# IMX8_LPDDR4.net
KiCad netlist of a schematic drawn in Altium Designer
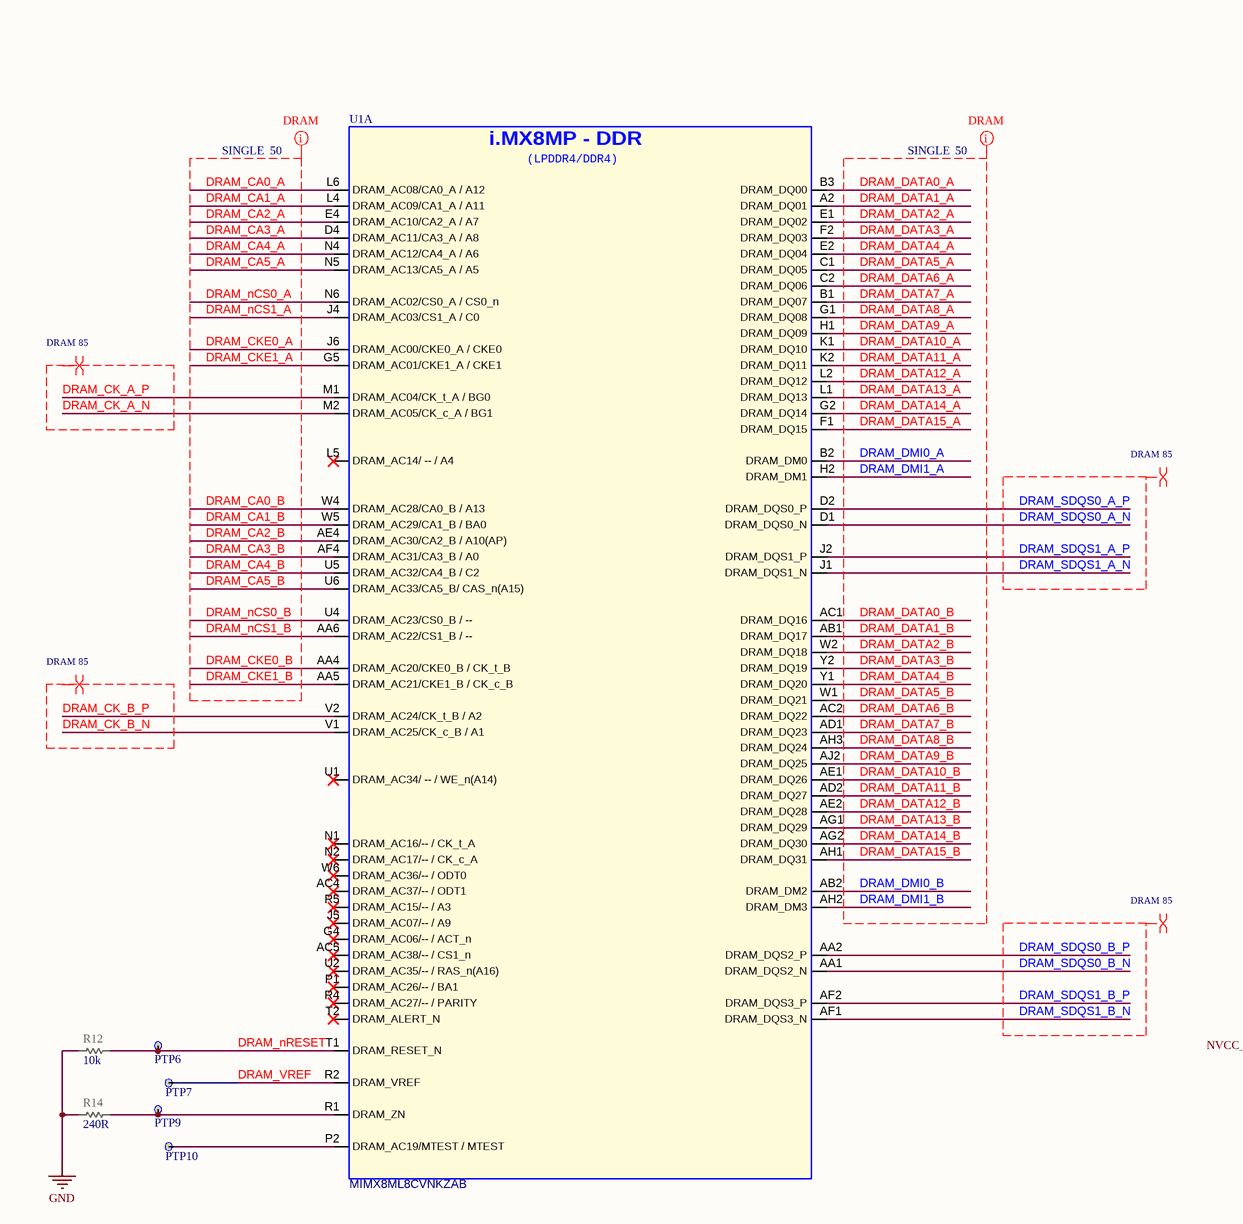
[diagram p0: IMX8_LPDDR4.SchDoc, top left]
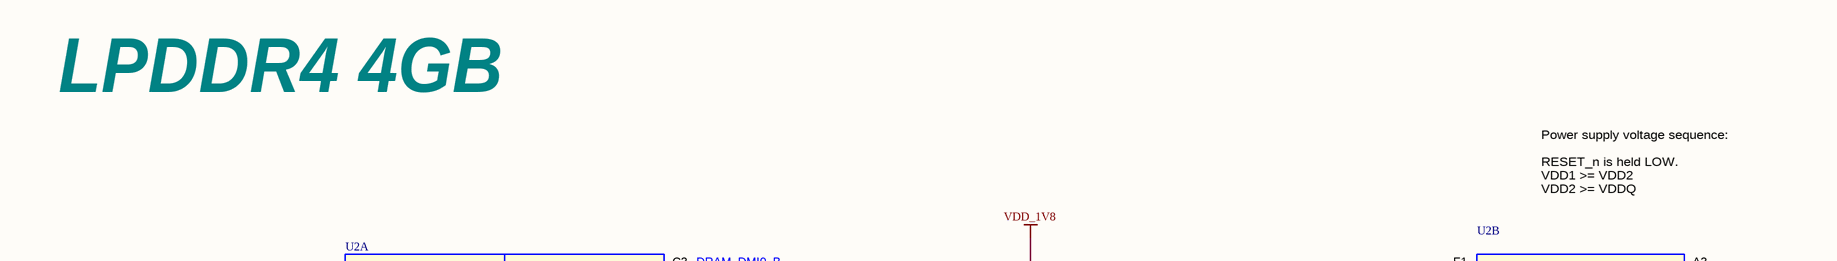
[diagram p1: IMX8_LPDDR4.SchDoc, top right]
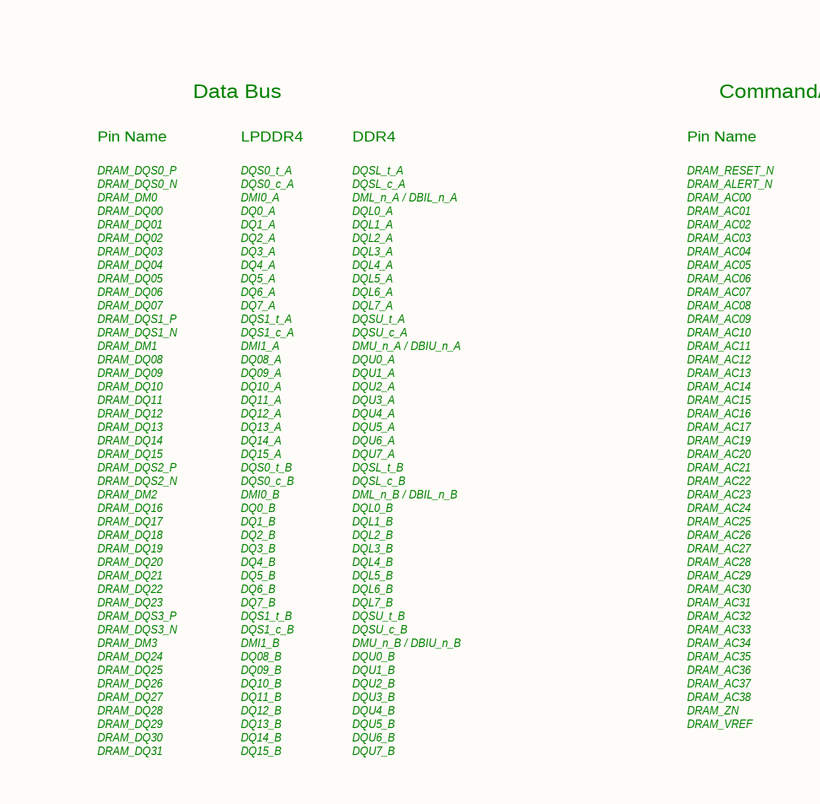
[diagram p2: IMX8_LPDDR4.SchDoc, bottom left]
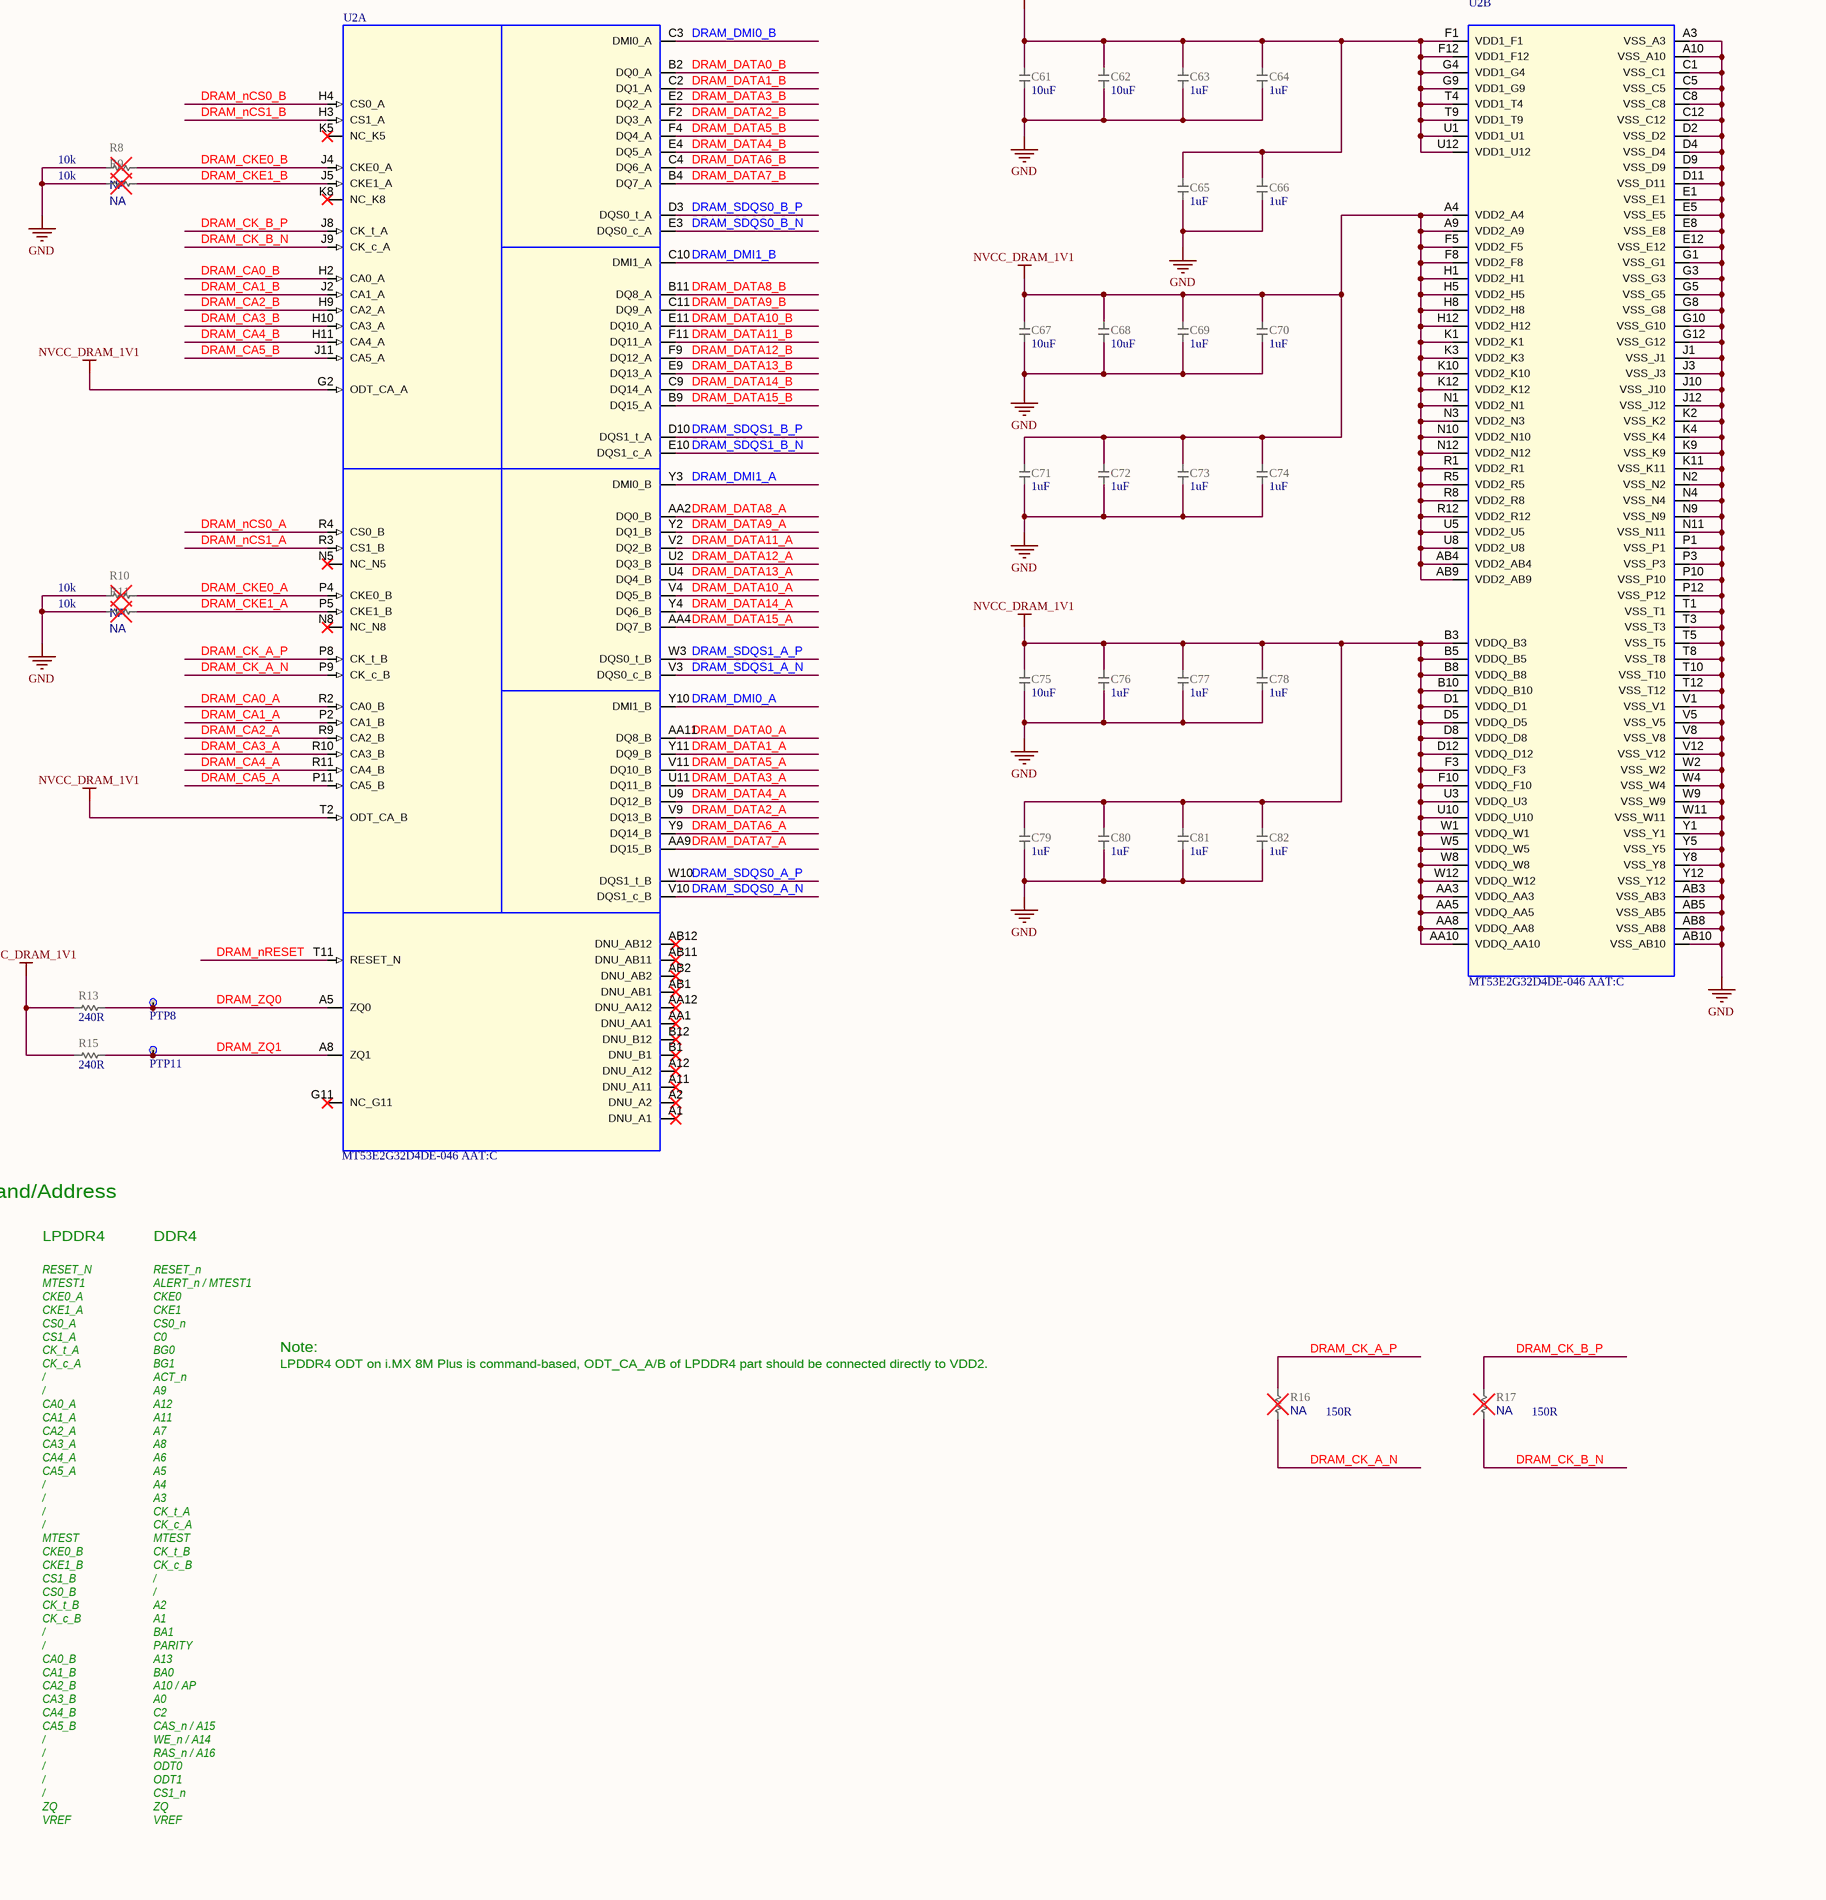
[diagram p3: IMX8_LPDDR4.SchDoc, bottom right]

(export (version "E")
  (design (tool "Eeschema 10.0.6"))
  (components
    (comp (ref "C61")
      (value "10uF")
      (footprint "CAP_0402_H09W07_UN1Q")
      (description "CAP")
      (fields (field (name "VOLTAGE") "6.3V") (field (name "TOLERANCE") "+/-20%"))
      (libsource (lib "robo_cam") (part "CMP-001-000883-14"))
    )
    (comp (ref "C62")
      (value "10uF")
      (footprint "CAP_0402_H09W07_UN1Q")
      (description "CAP")
      (fields (field (name "VOLTAGE") "6.3V") (field (name "TOLERANCE") "+/-20%"))
      (libsource (lib "robo_cam") (part "CMP-001-000883-14"))
    )
    (comp (ref "C63")
      (value "1uF")
      (footprint "CAP_0201_UN1Q")
      (description "CAP")
      (fields (field (name "PART NUMBER") "KGM03CS61A105MH") (field (name "MANUFACTURER") "KYOCERA AVX"))
      (libsource (lib "robo_cam") (part "CMP-001-000336-15"))
    )
    (comp (ref "C64")
      (value "1uF")
      (footprint "CAP_0201_UN1Q")
      (description "CAP")
      (fields (field (name "PART NUMBER") "KGM03CS61A105MH") (field (name "MANUFACTURER") "KYOCERA AVX"))
      (libsource (lib "robo_cam") (part "CMP-001-000336-15"))
    )
    (comp (ref "C65")
      (value "1uF")
      (footprint "CAP_0201_UN1Q")
      (description "CAP")
      (fields (field (name "PART NUMBER") "KGM03CS61A105MH") (field (name "MANUFACTURER") "KYOCERA AVX"))
      (libsource (lib "robo_cam") (part "CMP-001-000336-15"))
    )
    (comp (ref "C66")
      (value "1uF")
      (footprint "CAP_0201_UN1Q")
      (description "CAP")
      (fields (field (name "PART NUMBER") "KGM03CS61A105MH") (field (name "MANUFACTURER") "KYOCERA AVX"))
      (libsource (lib "robo_cam") (part "CMP-001-000336-15"))
    )
    (comp (ref "C67")
      (value "10uF")
      (footprint "CAP_0402_H09W07_UN1Q")
      (description "CAP")
      (fields (field (name "VOLTAGE") "6.3V") (field (name "TOLERANCE") "+/-20%"))
      (libsource (lib "robo_cam") (part "CMP-001-000883-14"))
    )
    (comp (ref "C68")
      (value "10uF")
      (footprint "CAP_0402_H09W07_UN1Q")
      (description "CAP")
      (fields (field (name "VOLTAGE") "6.3V") (field (name "TOLERANCE") "+/-20%"))
      (libsource (lib "robo_cam") (part "CMP-001-000883-14"))
    )
    (comp (ref "C69")
      (value "1uF")
      (footprint "CAP_0201_UN1Q")
      (description "CAP")
      (fields (field (name "PART NUMBER") "KGM03CS61A105MH") (field (name "MANUFACTURER") "KYOCERA AVX"))
      (libsource (lib "robo_cam") (part "CMP-001-000336-15"))
    )
    (comp (ref "C70")
      (value "1uF")
      (footprint "CAP_0201_UN1Q")
      (description "CAP")
      (fields (field (name "PART NUMBER") "KGM03CS61A105MH") (field (name "MANUFACTURER") "KYOCERA AVX"))
      (libsource (lib "robo_cam") (part "CMP-001-000336-15"))
    )
    (comp (ref "C71")
      (value "1uF")
      (footprint "CAP_0201_UN1Q")
      (description "CAP")
      (fields (field (name "PART NUMBER") "KGM03CS61A105MH") (field (name "MANUFACTURER") "KYOCERA AVX"))
      (libsource (lib "robo_cam") (part "CMP-001-000336-15"))
    )
    (comp (ref "C72")
      (value "1uF")
      (footprint "CAP_0201_UN1Q")
      (description "CAP")
      (fields (field (name "PART NUMBER") "KGM03CS61A105MH") (field (name "MANUFACTURER") "KYOCERA AVX"))
      (libsource (lib "robo_cam") (part "CMP-001-000336-15"))
    )
    (comp (ref "C73")
      (value "1uF")
      (footprint "CAP_0201_UN1Q")
      (description "CAP")
      (fields (field (name "PART NUMBER") "KGM03CS61A105MH") (field (name "MANUFACTURER") "KYOCERA AVX"))
      (libsource (lib "robo_cam") (part "CMP-001-000336-15"))
    )
    (comp (ref "C74")
      (value "1uF")
      (footprint "CAP_0201_UN1Q")
      (description "CAP")
      (fields (field (name "PART NUMBER") "KGM03CS61A105MH") (field (name "MANUFACTURER") "KYOCERA AVX"))
      (libsource (lib "robo_cam") (part "CMP-001-000336-15"))
    )
    (comp (ref "C75")
      (value "10uF")
      (footprint "CAP_0402_H09W07_UN1Q")
      (description "CAP")
      (fields (field (name "VOLTAGE") "6.3V") (field (name "TOLERANCE") "+/-20%"))
      (libsource (lib "robo_cam") (part "CMP-001-000883-14"))
    )
    (comp (ref "C76")
      (value "1uF")
      (footprint "CAP_0201_UN1Q")
      (description "CAP")
      (fields (field (name "PART NUMBER") "KGM03CS61A105MH") (field (name "MANUFACTURER") "KYOCERA AVX"))
      (libsource (lib "robo_cam") (part "CMP-001-000336-15"))
    )
    (comp (ref "C77")
      (value "1uF")
      (footprint "CAP_0201_UN1Q")
      (description "CAP")
      (fields (field (name "PART NUMBER") "KGM03CS61A105MH") (field (name "MANUFACTURER") "KYOCERA AVX"))
      (libsource (lib "robo_cam") (part "CMP-001-000336-15"))
    )
    (comp (ref "C78")
      (value "1uF")
      (footprint "CAP_0201_UN1Q")
      (description "CAP")
      (fields (field (name "PART NUMBER") "KGM03CS61A105MH") (field (name "MANUFACTURER") "KYOCERA AVX"))
      (libsource (lib "robo_cam") (part "CMP-001-000336-15"))
    )
    (comp (ref "C79")
      (value "1uF")
      (footprint "CAP_0201_UN1Q")
      (description "CAP")
      (fields (field (name "PART NUMBER") "KGM03CS61A105MH") (field (name "MANUFACTURER") "KYOCERA AVX"))
      (libsource (lib "robo_cam") (part "CMP-001-000336-15"))
    )
    (comp (ref "C80")
      (value "1uF")
      (footprint "CAP_0201_UN1Q")
      (description "CAP")
      (fields (field (name "PART NUMBER") "KGM03CS61A105MH") (field (name "MANUFACTURER") "KYOCERA AVX"))
      (libsource (lib "robo_cam") (part "CMP-001-000336-15"))
    )
    (comp (ref "C81")
      (value "1uF")
      (footprint "CAP_0201_UN1Q")
      (description "CAP")
      (fields (field (name "PART NUMBER") "KGM03CS61A105MH") (field (name "MANUFACTURER") "KYOCERA AVX"))
      (libsource (lib "robo_cam") (part "CMP-001-000336-15"))
    )
    (comp (ref "C82")
      (value "1uF")
      (footprint "CAP_0201_UN1Q")
      (description "CAP")
      (fields (field (name "PART NUMBER") "KGM03CS61A105MH") (field (name "MANUFACTURER") "KYOCERA AVX"))
      (libsource (lib "robo_cam") (part "CMP-001-000336-15"))
    )
    (comp (ref "PTP6")
      (value "PTP_0.4mm")
      (footprint "PTP_0.4mm")
      (description "Production Testpoint 0.4mm. Flying probe. Use 1mm pitch.")
      (fields (field (name "PART NUMBER") "PTP 0.4mm"))
      (libsource (lib "robo_cam") (part "CMP-001-001296-3"))
    )
    (comp (ref "PTP7")
      (value "PTP_0.4mm")
      (footprint "PTP_0.4mm")
      (description "Production Testpoint 0.4mm. Flying probe. Use 1mm pitch.")
      (fields (field (name "PART NUMBER") "PTP 0.4mm"))
      (libsource (lib "robo_cam") (part "CMP-001-001296-3"))
    )
    (comp (ref "PTP8")
      (value "PTP_0.4mm")
      (footprint "PTP_0.4mm")
      (description "Production Testpoint 0.4mm. Flying probe. Use 1mm pitch.")
      (fields (field (name "PART NUMBER") "PTP 0.4mm"))
      (libsource (lib "robo_cam") (part "CMP-001-001296-3"))
    )
    (comp (ref "PTP9")
      (value "PTP_0.4mm")
      (footprint "PTP_0.4mm")
      (description "Production Testpoint 0.4mm. Flying probe. Use 1mm pitch.")
      (fields (field (name "PART NUMBER") "PTP 0.4mm"))
      (libsource (lib "robo_cam") (part "CMP-001-001296-3"))
    )
    (comp (ref "PTP10")
      (value "PTP_0.4mm")
      (footprint "PTP_0.4mm")
      (description "Production Testpoint 0.4mm. Flying probe. Use 1mm pitch.")
      (fields (field (name "PART NUMBER") "PTP 0.4mm"))
      (libsource (lib "robo_cam") (part "CMP-001-001296-3"))
    )
    (comp (ref "PTP11")
      (value "PTP_0.4mm")
      (footprint "PTP_0.4mm")
      (description "Production Testpoint 0.4mm. Flying probe. Use 1mm pitch.")
      (fields (field (name "PART NUMBER") "PTP 0.4mm"))
      (libsource (lib "robo_cam") (part "CMP-001-001296-3"))
    )
    (comp (ref "R8")
      (value "NA")
      (footprint "RES_0201_UN1Q")
      (description "Not Assembled - RES")
      (fields (field (name "Comment") "RES_0201_NA"))
      (libsource (lib "robo_cam") (part "CMP-001-000434-10"))
    )
    (comp (ref "R9")
      (value "NA")
      (footprint "RES_0201_UN1Q")
      (description "Not Assembled - RES")
      (fields (field (name "Comment") "RES_0201_NA"))
      (libsource (lib "robo_cam") (part "CMP-001-000434-10"))
    )
    (comp (ref "R10")
      (value "NA")
      (footprint "RES_0201_UN1Q")
      (description "Not Assembled - RES")
      (fields (field (name "Comment") "RES_0201_NA"))
      (libsource (lib "robo_cam") (part "CMP-001-000434-10"))
    )
    (comp (ref "R11")
      (value "NA")
      (footprint "RES_0201_UN1Q")
      (description "Not Assembled - RES")
      (fields (field (name "Comment") "RES_0201_NA"))
      (libsource (lib "robo_cam") (part "CMP-001-000434-10"))
    )
    (comp (ref "R12")
      (value "10k")
      (footprint "RES_0201_UN1Q")
      (description "RES")
      (fields (field (name "PART NUMBER") "RC0201FR-0710KL") (field (name "MANUFACTURER") "YAGEO"))
      (libsource (lib "robo_cam") (part "CMP-001-000446-13"))
    )
    (comp (ref "R13")
      (value "240R")
      (footprint "RES_0201_UN1Q")
      (description "RES")
      (fields (field (name "TOLERANCE") "1%") (field (name "PART NUMBER") "ERJ-1GEJ241C"))
      (libsource (lib "robo_cam") (part "CMP-001-000554-13"))
    )
    (comp (ref "R14")
      (value "240R")
      (footprint "RES_0201_UN1Q")
      (description "RES")
      (fields (field (name "TOLERANCE") "1%") (field (name "PART NUMBER") "ERJ-1GEJ241C"))
      (libsource (lib "robo_cam") (part "CMP-001-000554-13"))
    )
    (comp (ref "R15")
      (value "240R")
      (footprint "RES_0201_UN1Q")
      (description "RES")
      (fields (field (name "TOLERANCE") "1%") (field (name "PART NUMBER") "ERJ-1GEJ241C"))
      (libsource (lib "robo_cam") (part "CMP-001-000554-13"))
    )
    (comp (ref "R16")
      (value "NA")
      (footprint "RES_0201_UN1Q")
      (description "Not Assembled - RES")
      (fields (field (name "Comment") "RES_0201_NA"))
      (libsource (lib "robo_cam") (part "CMP-001-000434-10"))
    )
    (comp (ref "R17")
      (value "NA")
      (footprint "RES_0201_UN1Q")
      (description "Not Assembled - RES")
      (fields (field (name "Comment") "RES_0201_NA"))
      (libsource (lib "robo_cam") (part "CMP-001-000434-10"))
    )
    (comp (ref "U1")
      (value "MIMX8ML8CVNKZAB")
      (footprint "BGA548C50P29X29_1500X1500X148")
      (description "CPU QUAD CORTEX A53+M4 1.6GHZ BGA548 Industrial")
      (fields
        (field (name "MANUFACTURER") "NXP Semiconductors")
        (field (name "PART NUMBER") "MIMX8ML8CVNKZAB")
        (field (name "SOURCE") "UUDET_KOMPONENTIT.SchLib")
      )
      (libsource (lib "robo_cam") (part "CMP-001-000983-8"))
    )
    (comp (ref "U2")
      (value "MT53E2G32D4DE-046 AAT:C")
      (footprint "BGA200C65P12X22_1000X1450X114")
      (description "MEM LPDDR4 SDRAM 2133MHz 2Gx32Gb 1.1V")
      (fields (field (name "MANUFACTURER") "Micron") (field (name "PART NUMBER") "MT53E2G32D4DE-046 AAT:C"))
      (libsource (lib "robo_cam") (part "CMP-001-001446-1"))
    )
  )
  (nets
    (net (code "1") (name "/DRAM_CA0_A") (class "Default")
      (node (ref "U1") (pin "L6") (pinfunction "DRAM_AC08/CA0_A_/_A12_L6") (pintype "passive"))
      (node (ref "U2") (pin "R2") (pinfunction "CA0_B_R2") (pintype "input"))
    )
    (net (code "2") (name "/DRAM_CA0_B") (class "Default")
      (node (ref "U1") (pin "W4") (pinfunction "DRAM_AC28/CA0_B_/_A13_W4") (pintype "passive"))
      (node (ref "U2") (pin "H2") (pinfunction "CA0_A_H2") (pintype "input"))
    )
    (net (code "3") (name "/DRAM_CA1_A") (class "Default")
      (node (ref "U1") (pin "L4") (pinfunction "DRAM_AC09/CA1_A_/_A11_L4") (pintype "passive"))
      (node (ref "U2") (pin "P2") (pinfunction "CA1_B_P2") (pintype "input"))
    )
    (net (code "4") (name "/DRAM_CA1_B") (class "Default")
      (node (ref "U1") (pin "W5") (pinfunction "DRAM_AC29/CA1_B_/_BA0_W5") (pintype "passive"))
      (node (ref "U2") (pin "J2") (pinfunction "CA1_A_J2") (pintype "input"))
    )
    (net (code "5") (name "/DRAM_CA2_A") (class "Default")
      (node (ref "U1") (pin "E4") (pinfunction "DRAM_AC10/CA2_A_/_A7_E4") (pintype "passive"))
      (node (ref "U2") (pin "R9") (pinfunction "CA2_B_R9") (pintype "input"))
    )
    (net (code "6") (name "/DRAM_CA2_B") (class "Default")
      (node (ref "U1") (pin "AE4") (pinfunction "DRAM_AC30/CA2_B_/_A10(AP)_AE4") (pintype "passive"))
      (node (ref "U2") (pin "H9") (pinfunction "CA2_A_H9") (pintype "input"))
    )
    (net (code "7") (name "/DRAM_CA3_A") (class "Default")
      (node (ref "U1") (pin "D4") (pinfunction "DRAM_AC11/CA3_A_/_A8_D4") (pintype "passive"))
      (node (ref "U2") (pin "R10") (pinfunction "CA3_B_R10") (pintype "input"))
    )
    (net (code "8") (name "/DRAM_CA3_B") (class "Default")
      (node (ref "U1") (pin "AF4") (pinfunction "DRAM_AC31/CA3_B_/_A0_AF4") (pintype "passive"))
      (node (ref "U2") (pin "H10") (pinfunction "CA3_A_H10") (pintype "input"))
    )
    (net (code "9") (name "/DRAM_CA4_A") (class "Default")
      (node (ref "U1") (pin "N4") (pinfunction "DRAM_AC12/CA4_A_/_A6_N4") (pintype "passive"))
      (node (ref "U2") (pin "R11") (pinfunction "CA4_B_R11") (pintype "input"))
    )
    (net (code "10") (name "/DRAM_CA4_B") (class "Default")
      (node (ref "U1") (pin "U5") (pinfunction "DRAM_AC32/CA4_B_/_C2_U5") (pintype "passive"))
      (node (ref "U2") (pin "H11") (pinfunction "CA4_A_H11") (pintype "input"))
    )
    (net (code "11") (name "/DRAM_CA5_A") (class "Default")
      (node (ref "U1") (pin "N5") (pinfunction "DRAM_AC13/CA5_A_/_A5_N5") (pintype "passive"))
      (node (ref "U2") (pin "P11") (pinfunction "CA5_B_P11") (pintype "input"))
    )
    (net (code "12") (name "/DRAM_CA5_B") (class "Default")
      (node (ref "U1") (pin "U6") (pinfunction "DRAM_AC33/CA5_B/_CAS_n(A15)_U6") (pintype "passive"))
      (node (ref "U2") (pin "J11") (pinfunction "CA5_A_J11") (pintype "input"))
    )
    (net (code "13") (name "/DRAM_CKE0_A") (class "Default")
      (node (ref "R10") (pin "2") (pinfunction "2_2") (pintype "passive"))
      (node (ref "U1") (pin "J6") (pinfunction "DRAM_AC00/CKE0_A_/_CKE0_J6") (pintype "passive"))
      (node (ref "U2") (pin "P4") (pinfunction "CKE0_B_P4") (pintype "input"))
    )
    (net (code "14") (name "/DRAM_CKE0_B") (class "Default")
      (node (ref "R8") (pin "2") (pinfunction "2_2") (pintype "passive"))
      (node (ref "U1") (pin "AA4") (pinfunction "DRAM_AC20/CKE0_B_/_CK_t_B_AA4") (pintype "passive"))
      (node (ref "U2") (pin "J4") (pinfunction "CKE0_A_J4") (pintype "input"))
    )
    (net (code "15") (name "/DRAM_CKE1_A") (class "Default")
      (node (ref "R11") (pin "2") (pinfunction "2_2") (pintype "passive"))
      (node (ref "U1") (pin "G5") (pinfunction "DRAM_AC01/CKE1_A_/_CKE1_G5") (pintype "passive"))
      (node (ref "U2") (pin "P5") (pinfunction "CKE1_B_P5") (pintype "input"))
    )
    (net (code "16") (name "/DRAM_CKE1_B") (class "Default")
      (node (ref "R9") (pin "2") (pinfunction "2_2") (pintype "passive"))
      (node (ref "U1") (pin "AA5") (pinfunction "DRAM_AC21/CKE1_B_/_CK_c_B_AA5") (pintype "passive"))
      (node (ref "U2") (pin "J5") (pinfunction "CKE1_A_J5") (pintype "input"))
    )
    (net (code "17") (name "/DRAM_CK_A_N") (class "Default")
      (node (ref "R16") (pin "1") (pinfunction "1_1") (pintype "passive"))
      (node (ref "U1") (pin "M2") (pinfunction "DRAM_AC05/CK_c_A_/_BG1_M2") (pintype "passive"))
      (node (ref "U2") (pin "P9") (pinfunction "CK_c_B_P9") (pintype "input"))
    )
    (net (code "18") (name "/DRAM_CK_A_P") (class "Default")
      (node (ref "R16") (pin "2") (pinfunction "2_2") (pintype "passive"))
      (node (ref "U1") (pin "M1") (pinfunction "DRAM_AC04/CK_t_A_/_BG0_M1") (pintype "passive"))
      (node (ref "U2") (pin "P8") (pinfunction "CK_t_B_P8") (pintype "input"))
    )
    (net (code "19") (name "/DRAM_CK_B_N") (class "Default")
      (node (ref "R17") (pin "1") (pinfunction "1_1") (pintype "passive"))
      (node (ref "U1") (pin "V1") (pinfunction "DRAM_AC25/CK_c_B_/_A1_V1") (pintype "passive"))
      (node (ref "U2") (pin "J9") (pinfunction "CK_c_A_J9") (pintype "input"))
    )
    (net (code "20") (name "/DRAM_CK_B_P") (class "Default")
      (node (ref "R17") (pin "2") (pinfunction "2_2") (pintype "passive"))
      (node (ref "U1") (pin "V2") (pinfunction "DRAM_AC24/CK_t_B_/_A2_V2") (pintype "passive"))
      (node (ref "U2") (pin "J8") (pinfunction "CK_t_A_J8") (pintype "input"))
    )
    (net (code "21") (name "/DRAM_DATA0_A") (class "Default")
      (node (ref "U1") (pin "B3") (pinfunction "DRAM_DQ00_B3") (pintype "passive"))
      (node (ref "U2") (pin "AA11") (pinfunction "DQ8_B_AA11") (pintype "bidirectional"))
    )
    (net (code "22") (name "/DRAM_DATA0_B") (class "Default")
      (node (ref "U1") (pin "AC1") (pinfunction "DRAM_DQ16_AC1") (pintype "passive"))
      (node (ref "U2") (pin "B2") (pinfunction "DQ0_A_B2") (pintype "bidirectional"))
    )
    (net (code "23") (name "/DRAM_DATA1_A") (class "Default")
      (node (ref "U1") (pin "A2") (pinfunction "DRAM_DQ01_A2") (pintype "passive"))
      (node (ref "U2") (pin "Y11") (pinfunction "DQ9_B_Y11") (pintype "bidirectional"))
    )
    (net (code "24") (name "/DRAM_DATA1_B") (class "Default")
      (node (ref "U1") (pin "AB1") (pinfunction "DRAM_DQ17_AB1") (pintype "passive"))
      (node (ref "U2") (pin "C2") (pinfunction "DQ1_A_C2") (pintype "bidirectional"))
    )
    (net (code "25") (name "/DRAM_DATA2_A") (class "Default")
      (node (ref "U1") (pin "E1") (pinfunction "DRAM_DQ02_E1") (pintype "passive"))
      (node (ref "U2") (pin "V9") (pinfunction "DQ13_B_V9") (pintype "bidirectional"))
    )
    (net (code "26") (name "/DRAM_DATA2_B") (class "Default")
      (node (ref "U1") (pin "W2") (pinfunction "DRAM_DQ18_W2") (pintype "passive"))
      (node (ref "U2") (pin "F2") (pinfunction "DQ3_A_F2") (pintype "bidirectional"))
    )
    (net (code "27") (name "/DRAM_DATA3_A") (class "Default")
      (node (ref "U1") (pin "F2") (pinfunction "DRAM_DQ03_F2") (pintype "passive"))
      (node (ref "U2") (pin "U11") (pinfunction "DQ11_B_U11") (pintype "bidirectional"))
    )
    (net (code "28") (name "/DRAM_DATA3_B") (class "Default")
      (node (ref "U1") (pin "Y2") (pinfunction "DRAM_DQ19_Y2") (pintype "passive"))
      (node (ref "U2") (pin "E2") (pinfunction "DQ2_A_E2") (pintype "bidirectional"))
    )
    (net (code "29") (name "/DRAM_DATA4_A") (class "Default")
      (node (ref "U1") (pin "E2") (pinfunction "DRAM_DQ04_E2") (pintype "passive"))
      (node (ref "U2") (pin "U9") (pinfunction "DQ12_B_U9") (pintype "bidirectional"))
    )
    (net (code "30") (name "/DRAM_DATA4_B") (class "Default")
      (node (ref "U1") (pin "Y1") (pinfunction "DRAM_DQ20_Y1") (pintype "passive"))
      (node (ref "U2") (pin "E4") (pinfunction "DQ5_A_E4") (pintype "bidirectional"))
    )
    (net (code "31") (name "/DRAM_DATA5_A") (class "Default")
      (node (ref "U1") (pin "C1") (pinfunction "DRAM_DQ05_C1") (pintype "passive"))
      (node (ref "U2") (pin "V11") (pinfunction "DQ10_B_V11") (pintype "bidirectional"))
    )
    (net (code "32") (name "/DRAM_DATA5_B") (class "Default")
      (node (ref "U1") (pin "W1") (pinfunction "DRAM_DQ21_W1") (pintype "passive"))
      (node (ref "U2") (pin "F4") (pinfunction "DQ4_A_F4") (pintype "bidirectional"))
    )
    (net (code "33") (name "/DRAM_DATA6_A") (class "Default")
      (node (ref "U1") (pin "C2") (pinfunction "DRAM_DQ06_C2") (pintype "passive"))
      (node (ref "U2") (pin "Y9") (pinfunction "DQ14_B_Y9") (pintype "bidirectional"))
    )
    (net (code "34") (name "/DRAM_DATA6_B") (class "Default")
      (node (ref "U1") (pin "AC2") (pinfunction "DRAM_DQ22_AC2") (pintype "passive"))
      (node (ref "U2") (pin "C4") (pinfunction "DQ6_A_C4") (pintype "bidirectional"))
    )
    (net (code "35") (name "/DRAM_DATA7_A") (class "Default")
      (node (ref "U1") (pin "B1") (pinfunction "DRAM_DQ07_B1") (pintype "passive"))
      (node (ref "U2") (pin "AA9") (pinfunction "DQ15_B_AA9") (pintype "bidirectional"))
    )
    (net (code "36") (name "/DRAM_DATA7_B") (class "Default")
      (node (ref "U1") (pin "AD1") (pinfunction "DRAM_DQ23_AD1") (pintype "passive"))
      (node (ref "U2") (pin "B4") (pinfunction "DQ7_A_B4") (pintype "bidirectional"))
    )
    (net (code "37") (name "/DRAM_DATA8_A") (class "Default")
      (node (ref "U1") (pin "G1") (pinfunction "DRAM_DQ08_G1") (pintype "passive"))
      (node (ref "U2") (pin "AA2") (pinfunction "DQ0_B_AA2") (pintype "bidirectional"))
    )
    (net (code "38") (name "/DRAM_DATA8_B") (class "Default")
      (node (ref "U1") (pin "AH3") (pinfunction "DRAM_DQ24_AH3") (pintype "passive"))
      (node (ref "U2") (pin "B11") (pinfunction "DQ8_A_B11") (pintype "bidirectional"))
    )
    (net (code "39") (name "/DRAM_DATA9_A") (class "Default")
      (node (ref "U1") (pin "H1") (pinfunction "DRAM_DQ09_H1") (pintype "passive"))
      (node (ref "U2") (pin "Y2") (pinfunction "DQ1_B_Y2") (pintype "bidirectional"))
    )
    (net (code "40") (name "/DRAM_DATA9_B") (class "Default")
      (node (ref "U1") (pin "AJ2") (pinfunction "DRAM_DQ25_AJ2") (pintype "passive"))
      (node (ref "U2") (pin "C11") (pinfunction "DQ9_A_C11") (pintype "bidirectional"))
    )
    (net (code "41") (name "/DRAM_DATA10_A") (class "Default")
      (node (ref "U1") (pin "K1") (pinfunction "DRAM_DQ10_K1") (pintype "passive"))
      (node (ref "U2") (pin "V4") (pinfunction "DQ5_B_V4") (pintype "bidirectional"))
    )
    (net (code "42") (name "/DRAM_DATA10_B") (class "Default")
      (node (ref "U1") (pin "AE1") (pinfunction "DRAM_DQ26_AE1") (pintype "passive"))
      (node (ref "U2") (pin "E11") (pinfunction "DQ10_A_E11") (pintype "bidirectional"))
    )
    (net (code "43") (name "/DRAM_DATA11_A") (class "Default")
      (node (ref "U1") (pin "K2") (pinfunction "DRAM_DQ11_K2") (pintype "passive"))
      (node (ref "U2") (pin "V2") (pinfunction "DQ2_B_V2") (pintype "bidirectional"))
    )
    (net (code "44") (name "/DRAM_DATA11_B") (class "Default")
      (node (ref "U1") (pin "AD2") (pinfunction "DRAM_DQ27_AD2") (pintype "passive"))
      (node (ref "U2") (pin "F11") (pinfunction "DQ11_A_F11") (pintype "bidirectional"))
    )
    (net (code "45") (name "/DRAM_DATA12_A") (class "Default")
      (node (ref "U1") (pin "L2") (pinfunction "DRAM_DQ12_L2") (pintype "passive"))
      (node (ref "U2") (pin "U2") (pinfunction "DQ3_B_U2") (pintype "bidirectional"))
    )
    (net (code "46") (name "/DRAM_DATA12_B") (class "Default")
      (node (ref "U1") (pin "AE2") (pinfunction "DRAM_DQ28_AE2") (pintype "passive"))
      (node (ref "U2") (pin "F9") (pinfunction "DQ12_A_F9") (pintype "bidirectional"))
    )
    (net (code "47") (name "/DRAM_DATA13_A") (class "Default")
      (node (ref "U1") (pin "L1") (pinfunction "DRAM_DQ13_L1") (pintype "passive"))
      (node (ref "U2") (pin "U4") (pinfunction "DQ4_B_U4") (pintype "bidirectional"))
    )
    (net (code "48") (name "/DRAM_DATA13_B") (class "Default")
      (node (ref "U1") (pin "AG1") (pinfunction "DRAM_DQ29_AG1") (pintype "passive"))
      (node (ref "U2") (pin "E9") (pinfunction "DQ13_A_E9") (pintype "bidirectional"))
    )
    (net (code "49") (name "/DRAM_DATA14_A") (class "Default")
      (node (ref "U1") (pin "G2") (pinfunction "DRAM_DQ14_G2") (pintype "passive"))
      (node (ref "U2") (pin "Y4") (pinfunction "DQ6_B_Y4") (pintype "bidirectional"))
    )
    (net (code "50") (name "/DRAM_DATA14_B") (class "Default")
      (node (ref "U1") (pin "AG2") (pinfunction "DRAM_DQ30_AG2") (pintype "passive"))
      (node (ref "U2") (pin "C9") (pinfunction "DQ14_A_C9") (pintype "bidirectional"))
    )
    (net (code "51") (name "/DRAM_DATA15_A") (class "Default")
      (node (ref "U1") (pin "F1") (pinfunction "DRAM_DQ15_F1") (pintype "passive"))
      (node (ref "U2") (pin "AA4") (pinfunction "DQ7_B_AA4") (pintype "bidirectional"))
    )
    (net (code "52") (name "/DRAM_DATA15_B") (class "Default")
      (node (ref "U1") (pin "AH1") (pinfunction "DRAM_DQ31_AH1") (pintype "passive"))
      (node (ref "U2") (pin "B9") (pinfunction "DQ15_A_B9") (pintype "bidirectional"))
    )
    (net (code "53") (name "/DRAM_DMI0_A") (class "Default")
      (node (ref "U1") (pin "B2") (pinfunction "DRAM_DM0_B2") (pintype "passive"))
      (node (ref "U2") (pin "Y10") (pinfunction "DMI1_B_Y10") (pintype "bidirectional"))
    )
    (net (code "54") (name "/DRAM_DMI0_B") (class "Default")
      (node (ref "U1") (pin "AB2") (pinfunction "DRAM_DM2_AB2") (pintype "passive"))
      (node (ref "U2") (pin "C3") (pinfunction "DMI0_A_C3") (pintype "bidirectional"))
    )
    (net (code "55") (name "/DRAM_DMI1_A") (class "Default")
      (node (ref "U1") (pin "H2") (pinfunction "DRAM_DM1_H2") (pintype "passive"))
      (node (ref "U2") (pin "Y3") (pinfunction "DMI0_B_Y3") (pintype "bidirectional"))
    )
    (net (code "56") (name "/DRAM_DMI1_B") (class "Default")
      (node (ref "U1") (pin "AH2") (pinfunction "DRAM_DM3_AH2") (pintype "passive"))
      (node (ref "U2") (pin "C10") (pinfunction "DMI1_A_C10") (pintype "bidirectional"))
    )
    (net (code "57") (name "/DRAM_SDQS0_A_N") (class "Default")
      (node (ref "U1") (pin "D1") (pinfunction "DRAM_DQS0_N_D1") (pintype "passive"))
      (node (ref "U2") (pin "V10") (pinfunction "DQS1_c_B_V10") (pintype "bidirectional"))
    )
    (net (code "58") (name "/DRAM_SDQS0_A_P") (class "Default")
      (node (ref "U1") (pin "D2") (pinfunction "DRAM_DQS0_P_D2") (pintype "passive"))
      (node (ref "U2") (pin "W10") (pinfunction "DQS1_t_B_W10") (pintype "bidirectional"))
    )
    (net (code "59") (name "/DRAM_SDQS0_B_N") (class "Default")
      (node (ref "U1") (pin "AA1") (pinfunction "DRAM_DQS2_N_AA1") (pintype "passive"))
      (node (ref "U2") (pin "E3") (pinfunction "DQS0_c_A_E3") (pintype "bidirectional"))
    )
    (net (code "60") (name "/DRAM_SDQS0_B_P") (class "Default")
      (node (ref "U1") (pin "AA2") (pinfunction "DRAM_DQS2_P_AA2") (pintype "passive"))
      (node (ref "U2") (pin "D3") (pinfunction "DQS0_t_A_D3") (pintype "bidirectional"))
    )
    (net (code "61") (name "/DRAM_SDQS1_A_N") (class "Default")
      (node (ref "U1") (pin "J1") (pinfunction "DRAM_DQS1_N_J1") (pintype "passive"))
      (node (ref "U2") (pin "V3") (pinfunction "DQS0_c_B_V3") (pintype "bidirectional"))
    )
    (net (code "62") (name "/DRAM_SDQS1_A_P") (class "Default")
      (node (ref "U1") (pin "J2") (pinfunction "DRAM_DQS1_P_J2") (pintype "passive"))
      (node (ref "U2") (pin "W3") (pinfunction "DQS0_t_B_W3") (pintype "bidirectional"))
    )
    (net (code "63") (name "/DRAM_SDQS1_B_N") (class "Default")
      (node (ref "U1") (pin "AF1") (pinfunction "DRAM_DQS3_N_AF1") (pintype "passive"))
      (node (ref "U2") (pin "E10") (pinfunction "DQS1_c_A_E10") (pintype "bidirectional"))
    )
    (net (code "64") (name "/DRAM_SDQS1_B_P") (class "Default")
      (node (ref "U1") (pin "AF2") (pinfunction "DRAM_DQS3_P_AF2") (pintype "passive"))
      (node (ref "U2") (pin "D10") (pinfunction "DQS1_t_A_D10") (pintype "bidirectional"))
    )
    (net (code "65") (name "/DRAM_VREF") (class "Default")
      (node (ref "PTP7") (pin "1") (pinfunction "TP_1") (pintype "passive"))
      (node (ref "U1") (pin "R2") (pinfunction "DRAM_VREF_R2") (pintype "passive"))
    )
    (net (code "66") (name "/DRAM_ZQ0") (class "Default")
      (node (ref "PTP8") (pin "1") (pinfunction "TP_1") (pintype "passive"))
      (node (ref "R13") (pin "2") (pinfunction "2_2") (pintype "passive"))
      (node (ref "U2") (pin "A5") (pinfunction "ZQ0_A5") (pintype "passive"))
    )
    (net (code "67") (name "/DRAM_ZQ1") (class "Default")
      (node (ref "PTP11") (pin "1") (pinfunction "TP_1") (pintype "passive"))
      (node (ref "R15") (pin "2") (pinfunction "2_2") (pintype "passive"))
      (node (ref "U2") (pin "A8") (pinfunction "ZQ1_A8") (pintype "passive"))
    )
    (net (code "68") (name "/DRAM_nCS0_A") (class "Default")
      (node (ref "U1") (pin "N6") (pinfunction "DRAM_AC02/CS0_A_/_CS0_n_N6") (pintype "passive"))
      (node (ref "U2") (pin "R4") (pinfunction "CS0_B_R4") (pintype "input"))
    )
    (net (code "69") (name "/DRAM_nCS0_B") (class "Default")
      (node (ref "U1") (pin "U4") (pinfunction "DRAM_AC23/CS0_B_/_--_U4") (pintype "passive"))
      (node (ref "U2") (pin "H4") (pinfunction "CS0_A_H4") (pintype "input"))
    )
    (net (code "70") (name "/DRAM_nCS1_A") (class "Default")
      (node (ref "U1") (pin "J4") (pinfunction "DRAM_AC03/CS1_A_/_C0_J4") (pintype "passive"))
      (node (ref "U2") (pin "R3") (pinfunction "CS1_B_R3") (pintype "input"))
    )
    (net (code "71") (name "/DRAM_nCS1_B") (class "Default")
      (node (ref "U1") (pin "AA6") (pinfunction "DRAM_AC22/CS1_B_/_--_AA6") (pintype "passive"))
      (node (ref "U2") (pin "H3") (pinfunction "CS1_A_H3") (pintype "input"))
    )
    (net (code "72") (name "/DRAM_nRESET") (class "Default")
      (node (ref "PTP6") (pin "1") (pinfunction "TP_1") (pintype "passive"))
      (node (ref "R12") (pin "2") (pinfunction "2_2") (pintype "passive"))
      (node (ref "U1") (pin "T1") (pinfunction "DRAM_RESET_N_T1") (pintype "passive"))
      (node (ref "U2") (pin "T11") (pinfunction "RESET_N_T11") (pintype "input"))
    )
    (net (code "73") (name "GND") (class "Default")
      (node (ref "C61") (pin "2") (pinfunction "2_2") (pintype "passive"))
      (node (ref "C62") (pin "2") (pinfunction "2_2") (pintype "passive"))
      (node (ref "C63") (pin "2") (pinfunction "2_2") (pintype "passive"))
      (node (ref "C64") (pin "2") (pinfunction "2_2") (pintype "passive"))
      (node (ref "C65") (pin "2") (pinfunction "2_2") (pintype "passive"))
      (node (ref "C66") (pin "2") (pinfunction "2_2") (pintype "passive"))
      (node (ref "C67") (pin "2") (pinfunction "2_2") (pintype "passive"))
      (node (ref "C68") (pin "2") (pinfunction "2_2") (pintype "passive"))
      (node (ref "C69") (pin "2") (pinfunction "2_2") (pintype "passive"))
      (node (ref "C70") (pin "2") (pinfunction "2_2") (pintype "passive"))
      (node (ref "C71") (pin "2") (pinfunction "2_2") (pintype "passive"))
      (node (ref "C72") (pin "2") (pinfunction "2_2") (pintype "passive"))
      (node (ref "C73") (pin "2") (pinfunction "2_2") (pintype "passive"))
      (node (ref "C74") (pin "2") (pinfunction "2_2") (pintype "passive"))
      (node (ref "C75") (pin "2") (pinfunction "2_2") (pintype "passive"))
      (node (ref "C76") (pin "2") (pinfunction "2_2") (pintype "passive"))
      (node (ref "C77") (pin "2") (pinfunction "2_2") (pintype "passive"))
      (node (ref "C78") (pin "2") (pinfunction "2_2") (pintype "passive"))
      (node (ref "C79") (pin "2") (pinfunction "2_2") (pintype "passive"))
      (node (ref "C80") (pin "2") (pinfunction "2_2") (pintype "passive"))
      (node (ref "C81") (pin "2") (pinfunction "2_2") (pintype "passive"))
      (node (ref "C82") (pin "2") (pinfunction "2_2") (pintype "passive"))
      (node (ref "R10") (pin "1") (pinfunction "1_1") (pintype "passive"))
      (node (ref "R11") (pin "1") (pinfunction "1_1") (pintype "passive"))
      (node (ref "R12") (pin "1") (pinfunction "1_1") (pintype "passive"))
      (node (ref "R14") (pin "1") (pinfunction "1_1") (pintype "passive"))
      (node (ref "R8") (pin "1") (pinfunction "1_1") (pintype "passive"))
      (node (ref "R9") (pin "1") (pinfunction "1_1") (pintype "passive"))
      (node (ref "U2") (pin "A10") (pinfunction "VSS_A10_A10") (pintype "power_in"))
      (node (ref "U2") (pin "A3") (pinfunction "VSS_A3_A3") (pintype "power_in"))
      (node (ref "U2") (pin "AB10") (pinfunction "VSS_AB10_AB10") (pintype "power_in"))
      (node (ref "U2") (pin "AB3") (pinfunction "VSS_AB3_AB3") (pintype "power_in"))
      (node (ref "U2") (pin "AB5") (pinfunction "VSS_AB5_AB5") (pintype "power_in"))
      (node (ref "U2") (pin "AB8") (pinfunction "VSS_AB8_AB8") (pintype "power_in"))
      (node (ref "U2") (pin "C1") (pinfunction "VSS_C1_C1") (pintype "power_in"))
      (node (ref "U2") (pin "C12") (pinfunction "VSS_C12_C12") (pintype "power_in"))
      (node (ref "U2") (pin "C5") (pinfunction "VSS_C5_C5") (pintype "power_in"))
      (node (ref "U2") (pin "C8") (pinfunction "VSS_C8_C8") (pintype "power_in"))
      (node (ref "U2") (pin "D11") (pinfunction "VSS_D11_D11") (pintype "power_in"))
      (node (ref "U2") (pin "D2") (pinfunction "VSS_D2_D2") (pintype "power_in"))
      (node (ref "U2") (pin "D4") (pinfunction "VSS_D4_D4") (pintype "power_in"))
      (node (ref "U2") (pin "D9") (pinfunction "VSS_D9_D9") (pintype "power_in"))
      (node (ref "U2") (pin "E1") (pinfunction "VSS_E1_E1") (pintype "power_in"))
      (node (ref "U2") (pin "E12") (pinfunction "VSS_E12_E12") (pintype "power_in"))
      (node (ref "U2") (pin "E5") (pinfunction "VSS_E5_E5") (pintype "power_in"))
      (node (ref "U2") (pin "E8") (pinfunction "VSS_E8_E8") (pintype "power_in"))
      (node (ref "U2") (pin "G1") (pinfunction "VSS_G1_G1") (pintype "power_in"))
      (node (ref "U2") (pin "G10") (pinfunction "VSS_G10_G10") (pintype "power_in"))
      (node (ref "U2") (pin "G12") (pinfunction "VSS_G12_G12") (pintype "power_in"))
      (node (ref "U2") (pin "G3") (pinfunction "VSS_G3_G3") (pintype "power_in"))
      (node (ref "U2") (pin "G5") (pinfunction "VSS_G5_G5") (pintype "power_in"))
      (node (ref "U2") (pin "G8") (pinfunction "VSS_G8_G8") (pintype "power_in"))
      (node (ref "U2") (pin "J1") (pinfunction "VSS_J1_J1") (pintype "power_in"))
      (node (ref "U2") (pin "J10") (pinfunction "VSS_J10_J10") (pintype "power_in"))
      (node (ref "U2") (pin "J12") (pinfunction "VSS_J12_J12") (pintype "power_in"))
      (node (ref "U2") (pin "J3") (pinfunction "VSS_J3_J3") (pintype "power_in"))
      (node (ref "U2") (pin "K11") (pinfunction "VSS_K11_K11") (pintype "power_in"))
      (node (ref "U2") (pin "K2") (pinfunction "VSS_K2_K2") (pintype "power_in"))
      (node (ref "U2") (pin "K4") (pinfunction "VSS_K4_K4") (pintype "power_in"))
      (node (ref "U2") (pin "K9") (pinfunction "VSS_K9_K9") (pintype "power_in"))
      (node (ref "U2") (pin "N11") (pinfunction "VSS_N11_N11") (pintype "power_in"))
      (node (ref "U2") (pin "N2") (pinfunction "VSS_N2_N2") (pintype "power_in"))
      (node (ref "U2") (pin "N4") (pinfunction "VSS_N4_N4") (pintype "power_in"))
      (node (ref "U2") (pin "N9") (pinfunction "VSS_N9_N9") (pintype "power_in"))
      (node (ref "U2") (pin "P1") (pinfunction "VSS_P1_P1") (pintype "power_in"))
      (node (ref "U2") (pin "P10") (pinfunction "VSS_P10_P10") (pintype "power_in"))
      (node (ref "U2") (pin "P12") (pinfunction "VSS_P12_P12") (pintype "power_in"))
      (node (ref "U2") (pin "P3") (pinfunction "VSS_P3_P3") (pintype "power_in"))
      (node (ref "U2") (pin "T1") (pinfunction "VSS_T1_T1") (pintype "power_in"))
      (node (ref "U2") (pin "T10") (pinfunction "VSS_T10_T10") (pintype "power_in"))
      (node (ref "U2") (pin "T12") (pinfunction "VSS_T12_T12") (pintype "power_in"))
      (node (ref "U2") (pin "T3") (pinfunction "VSS_T3_T3") (pintype "power_in"))
      (node (ref "U2") (pin "T5") (pinfunction "VSS_T5_T5") (pintype "power_in"))
      (node (ref "U2") (pin "T8") (pinfunction "VSS_T8_T8") (pintype "power_in"))
      (node (ref "U2") (pin "V1") (pinfunction "VSS_V1_V1") (pintype "power_in"))
      (node (ref "U2") (pin "V12") (pinfunction "VSS_V12_V12") (pintype "power_in"))
      (node (ref "U2") (pin "V5") (pinfunction "VSS_V5_V5") (pintype "power_in"))
      (node (ref "U2") (pin "V8") (pinfunction "VSS_V8_V8") (pintype "power_in"))
      (node (ref "U2") (pin "W11") (pinfunction "VSS_W11_W11") (pintype "power_in"))
      (node (ref "U2") (pin "W2") (pinfunction "VSS_W2_W2") (pintype "power_in"))
      (node (ref "U2") (pin "W4") (pinfunction "VSS_W4_W4") (pintype "power_in"))
      (node (ref "U2") (pin "W9") (pinfunction "VSS_W9_W9") (pintype "power_in"))
      (node (ref "U2") (pin "Y1") (pinfunction "VSS_Y1_Y1") (pintype "power_in"))
      (node (ref "U2") (pin "Y12") (pinfunction "VSS_Y12_Y12") (pintype "power_in"))
      (node (ref "U2") (pin "Y5") (pinfunction "VSS_Y5_Y5") (pintype "power_in"))
      (node (ref "U2") (pin "Y8") (pinfunction "VSS_Y8_Y8") (pintype "power_in"))
    )
    (net (code "74") (name "NVCC_DRAM_1V1") (class "Default")
      (node (ref "C67") (pin "1") (pinfunction "1_1") (pintype "passive"))
      (node (ref "C68") (pin "1") (pinfunction "1_1") (pintype "passive"))
      (node (ref "C69") (pin "1") (pinfunction "1_1") (pintype "passive"))
      (node (ref "C70") (pin "1") (pinfunction "1_1") (pintype "passive"))
      (node (ref "C71") (pin "1") (pinfunction "1_1") (pintype "passive"))
      (node (ref "C72") (pin "1") (pinfunction "1_1") (pintype "passive"))
      (node (ref "C73") (pin "1") (pinfunction "1_1") (pintype "passive"))
      (node (ref "C74") (pin "1") (pinfunction "1_1") (pintype "passive"))
      (node (ref "C75") (pin "1") (pinfunction "1_1") (pintype "passive"))
      (node (ref "C76") (pin "1") (pinfunction "1_1") (pintype "passive"))
      (node (ref "C77") (pin "1") (pinfunction "1_1") (pintype "passive"))
      (node (ref "C78") (pin "1") (pinfunction "1_1") (pintype "passive"))
      (node (ref "C79") (pin "1") (pinfunction "1_1") (pintype "passive"))
      (node (ref "C80") (pin "1") (pinfunction "1_1") (pintype "passive"))
      (node (ref "C81") (pin "1") (pinfunction "1_1") (pintype "passive"))
      (node (ref "C82") (pin "1") (pinfunction "1_1") (pintype "passive"))
      (node (ref "R13") (pin "1") (pinfunction "1_1") (pintype "passive"))
      (node (ref "R15") (pin "1") (pinfunction "1_1") (pintype "passive"))
      (node (ref "U2") (pin "A4") (pinfunction "VDD2_A4_A4") (pintype "power_in"))
      (node (ref "U2") (pin "A9") (pinfunction "VDD2_A9_A9") (pintype "power_in"))
      (node (ref "U2") (pin "AA10") (pinfunction "VDDQ_AA10_AA10") (pintype "power_in"))
      (node (ref "U2") (pin "AA3") (pinfunction "VDDQ_AA3_AA3") (pintype "power_in"))
      (node (ref "U2") (pin "AA5") (pinfunction "VDDQ_AA5_AA5") (pintype "power_in"))
      (node (ref "U2") (pin "AA8") (pinfunction "VDDQ_AA8_AA8") (pintype "power_in"))
      (node (ref "U2") (pin "AB4") (pinfunction "VDD2_AB4_AB4") (pintype "power_in"))
      (node (ref "U2") (pin "AB9") (pinfunction "VDD2_AB9_AB9") (pintype "power_in"))
      (node (ref "U2") (pin "B10") (pinfunction "VDDQ_B10_B10") (pintype "power_in"))
      (node (ref "U2") (pin "B3") (pinfunction "VDDQ_B3_B3") (pintype "power_in"))
      (node (ref "U2") (pin "B5") (pinfunction "VDDQ_B5_B5") (pintype "power_in"))
      (node (ref "U2") (pin "B8") (pinfunction "VDDQ_B8_B8") (pintype "power_in"))
      (node (ref "U2") (pin "D1") (pinfunction "VDDQ_D1_D1") (pintype "power_in"))
      (node (ref "U2") (pin "D12") (pinfunction "VDDQ_D12_D12") (pintype "power_in"))
      (node (ref "U2") (pin "D5") (pinfunction "VDDQ_D5_D5") (pintype "power_in"))
      (node (ref "U2") (pin "D8") (pinfunction "VDDQ_D8_D8") (pintype "power_in"))
      (node (ref "U2") (pin "F10") (pinfunction "VDDQ_F10_F10") (pintype "power_in"))
      (node (ref "U2") (pin "F3") (pinfunction "VDDQ_F3_F3") (pintype "power_in"))
      (node (ref "U2") (pin "F5") (pinfunction "VDD2_F5_F5") (pintype "power_in"))
      (node (ref "U2") (pin "F8") (pinfunction "VDD2_F8_F8") (pintype "power_in"))
      (node (ref "U2") (pin "G2") (pinfunction "ODT_CA_A_G2") (pintype "input"))
      (node (ref "U2") (pin "H1") (pinfunction "VDD2_H1_H1") (pintype "power_in"))
      (node (ref "U2") (pin "H12") (pinfunction "VDD2_H12_H12") (pintype "power_in"))
      (node (ref "U2") (pin "H5") (pinfunction "VDD2_H5_H5") (pintype "power_in"))
      (node (ref "U2") (pin "H8") (pinfunction "VDD2_H8_H8") (pintype "power_in"))
      (node (ref "U2") (pin "K1") (pinfunction "VDD2_K1_K1") (pintype "power_in"))
      (node (ref "U2") (pin "K10") (pinfunction "VDD2_K10_K10") (pintype "power_in"))
      (node (ref "U2") (pin "K12") (pinfunction "VDD2_K12_K12") (pintype "power_in"))
      (node (ref "U2") (pin "K3") (pinfunction "VDD2_K3_K3") (pintype "power_in"))
      (node (ref "U2") (pin "N1") (pinfunction "VDD2_N1_N1") (pintype "power_in"))
      (node (ref "U2") (pin "N10") (pinfunction "VDD2_N10_N10") (pintype "power_in"))
      (node (ref "U2") (pin "N12") (pinfunction "VDD2_N12_N12") (pintype "power_in"))
      (node (ref "U2") (pin "N3") (pinfunction "VDD2_N3_N3") (pintype "power_in"))
      (node (ref "U2") (pin "R1") (pinfunction "VDD2_R1_R1") (pintype "power_in"))
      (node (ref "U2") (pin "R12") (pinfunction "VDD2_R12_R12") (pintype "power_in"))
      (node (ref "U2") (pin "R5") (pinfunction "VDD2_R5_R5") (pintype "power_in"))
      (node (ref "U2") (pin "R8") (pinfunction "VDD2_R8_R8") (pintype "power_in"))
      (node (ref "U2") (pin "T2") (pinfunction "ODT_CA_B_T2") (pintype "input"))
      (node (ref "U2") (pin "U10") (pinfunction "VDDQ_U10_U10") (pintype "power_in"))
      (node (ref "U2") (pin "U3") (pinfunction "VDDQ_U3_U3") (pintype "power_in"))
      (node (ref "U2") (pin "U5") (pinfunction "VDD2_U5_U5") (pintype "power_in"))
      (node (ref "U2") (pin "U8") (pinfunction "VDD2_U8_U8") (pintype "power_in"))
      (node (ref "U2") (pin "W1") (pinfunction "VDDQ_W1_W1") (pintype "power_in"))
      (node (ref "U2") (pin "W12") (pinfunction "VDDQ_W12_W12") (pintype "power_in"))
      (node (ref "U2") (pin "W5") (pinfunction "VDDQ_W5_W5") (pintype "power_in"))
      (node (ref "U2") (pin "W8") (pinfunction "VDDQ_W8_W8") (pintype "power_in"))
    )
    (net (code "75") (name "Net-(PTP9-TP)") (class "Default")
      (node (ref "PTP9") (pin "1") (pinfunction "TP_1") (pintype "passive"))
      (node (ref "R14") (pin "2") (pinfunction "2_2") (pintype "passive"))
      (node (ref "U1") (pin "R1") (pinfunction "DRAM_ZN_R1") (pintype "passive"))
    )
    (net (code "76") (name "Net-(PTP10-TP)") (class "Default")
      (node (ref "PTP10") (pin "1") (pinfunction "TP_1") (pintype "passive"))
      (node (ref "U1") (pin "P2") (pinfunction "DRAM_AC19/MTEST_/_MTEST_P2") (pintype "passive"))
    )
    (net (code "77") (name "VDD_1V8") (class "Default")
      (node (ref "C61") (pin "1") (pinfunction "1_1") (pintype "passive"))
      (node (ref "C62") (pin "1") (pinfunction "1_1") (pintype "passive"))
      (node (ref "C63") (pin "1") (pinfunction "1_1") (pintype "passive"))
      (node (ref "C64") (pin "1") (pinfunction "1_1") (pintype "passive"))
      (node (ref "C65") (pin "1") (pinfunction "1_1") (pintype "passive"))
      (node (ref "C66") (pin "1") (pinfunction "1_1") (pintype "passive"))
      (node (ref "U2") (pin "F1") (pinfunction "VDD1_F1_F1") (pintype "power_in"))
      (node (ref "U2") (pin "F12") (pinfunction "VDD1_F12_F12") (pintype "power_in"))
      (node (ref "U2") (pin "G4") (pinfunction "VDD1_G4_G4") (pintype "power_in"))
      (node (ref "U2") (pin "G9") (pinfunction "VDD1_G9_G9") (pintype "power_in"))
      (node (ref "U2") (pin "T4") (pinfunction "VDD1_T4_T4") (pintype "power_in"))
      (node (ref "U2") (pin "T9") (pinfunction "VDD1_T9_T9") (pintype "power_in"))
      (node (ref "U2") (pin "U1") (pinfunction "VDD1_U1_U1") (pintype "power_in"))
      (node (ref "U2") (pin "U12") (pinfunction "VDD1_U12_U12") (pintype "power_in"))
    )
    (net (code "78") (name "unconnected-(U1A-DRAM_AC06{slash}--_{slash}_ACT_n-PadG4)") (class "Default")
      (node (ref "U1") (pin "G4") (pinfunction "DRAM_AC06/--_/_ACT_n_G4") (pintype "passive+no_connect"))
    )
    (net (code "79") (name "unconnected-(U1A-DRAM_AC07{slash}--_{slash}_A9-PadJ5)") (class "Default")
      (node (ref "U1") (pin "J5") (pinfunction "DRAM_AC07/--_/_A9_J5") (pintype "passive+no_connect"))
    )
    (net (code "80") (name "unconnected-(U1A-DRAM_AC14{slash}_--_{slash}_A4-PadL5)") (class "Default")
      (node (ref "U1") (pin "L5") (pinfunction "DRAM_AC14/_--_/_A4_L5") (pintype "passive+no_connect"))
    )
    (net (code "81") (name "unconnected-(U1A-DRAM_AC15{slash}--_{slash}_A3-PadR5)") (class "Default")
      (node (ref "U1") (pin "R5") (pinfunction "DRAM_AC15/--_/_A3_R5") (pintype "passive+no_connect"))
    )
    (net (code "82") (name "unconnected-(U1A-DRAM_AC16{slash}--_{slash}_CK_t_A-PadN1)") (class "Default")
      (node (ref "U1") (pin "N1") (pinfunction "DRAM_AC16/--_/_CK_t_A_N1") (pintype "passive+no_connect"))
    )
    (net (code "83") (name "unconnected-(U1A-DRAM_AC17{slash}--_{slash}_CK_c_A-PadN2)") (class "Default")
      (node (ref "U1") (pin "N2") (pinfunction "DRAM_AC17/--_/_CK_c_A_N2") (pintype "passive+no_connect"))
    )
    (net (code "84") (name "unconnected-(U1A-DRAM_AC26{slash}--_{slash}_BA1-PadP1)") (class "Default")
      (node (ref "U1") (pin "P1") (pinfunction "DRAM_AC26/--_/_BA1_P1") (pintype "passive+no_connect"))
    )
    (net (code "85") (name "unconnected-(U1A-DRAM_AC27{slash}--_{slash}_PARITY-PadR4)") (class "Default")
      (node (ref "U1") (pin "R4") (pinfunction "DRAM_AC27/--_/_PARITY_R4") (pintype "passive+no_connect"))
    )
    (net (code "86") (name "unconnected-(U1A-DRAM_AC34{slash}_--_{slash}_WE_n(A14)-PadU1)") (class "Default")
      (node (ref "U1") (pin "U1") (pinfunction "DRAM_AC34/_--_/_WE_n(A14)_U1") (pintype "passive+no_connect"))
    )
    (net (code "87") (name "unconnected-(U1A-DRAM_AC35{slash}--_{slash}_RAS_n(A16)-PadU2)") (class "Default")
      (node (ref "U1") (pin "U2") (pinfunction "DRAM_AC35/--_/_RAS_n(A16)_U2") (pintype "passive+no_connect"))
    )
    (net (code "88") (name "unconnected-(U1A-DRAM_AC36{slash}--_{slash}_ODT0-PadW6)") (class "Default")
      (node (ref "U1") (pin "W6") (pinfunction "DRAM_AC36/--_/_ODT0_W6") (pintype "passive+no_connect"))
    )
    (net (code "89") (name "unconnected-(U1A-DRAM_AC37{slash}--_{slash}_ODT1-PadAC4)") (class "Default")
      (node (ref "U1") (pin "AC4") (pinfunction "DRAM_AC37/--_/_ODT1_AC4") (pintype "passive+no_connect"))
    )
    (net (code "90") (name "unconnected-(U1A-DRAM_AC38{slash}--_{slash}_CS1_n-PadAC5)") (class "Default")
      (node (ref "U1") (pin "AC5") (pinfunction "DRAM_AC38/--_/_CS1_n_AC5") (pintype "passive+no_connect"))
    )
    (net (code "91") (name "unconnected-(U1A-DRAM_ALERT_N-PadT2)") (class "Default")
      (node (ref "U1") (pin "T2") (pinfunction "DRAM_ALERT_N_T2") (pintype "passive+no_connect"))
    )
    (net (code "92") (name "unconnected-(U2A-DNU_A1-PadA1)") (class "Default")
      (node (ref "U2") (pin "A1") (pinfunction "DNU_A1_A1") (pintype "passive+no_connect"))
    )
    (net (code "93") (name "unconnected-(U2A-DNU_A2-PadA2)") (class "Default")
      (node (ref "U2") (pin "A2") (pinfunction "DNU_A2_A2") (pintype "passive+no_connect"))
    )
    (net (code "94") (name "unconnected-(U2A-DNU_A11-PadA11)") (class "Default")
      (node (ref "U2") (pin "A11") (pinfunction "DNU_A11_A11") (pintype "passive+no_connect"))
    )
    (net (code "95") (name "unconnected-(U2A-DNU_A12-PadA12)") (class "Default")
      (node (ref "U2") (pin "A12") (pinfunction "DNU_A12_A12") (pintype "passive+no_connect"))
    )
    (net (code "96") (name "unconnected-(U2A-DNU_AA1-PadAA1)") (class "Default")
      (node (ref "U2") (pin "AA1") (pinfunction "DNU_AA1_AA1") (pintype "passive+no_connect"))
    )
    (net (code "97") (name "unconnected-(U2A-DNU_AA12-PadAA12)") (class "Default")
      (node (ref "U2") (pin "AA12") (pinfunction "DNU_AA12_AA12") (pintype "passive+no_connect"))
    )
    (net (code "98") (name "unconnected-(U2A-DNU_AB1-PadAB1)") (class "Default")
      (node (ref "U2") (pin "AB1") (pinfunction "DNU_AB1_AB1") (pintype "passive+no_connect"))
    )
    (net (code "99") (name "unconnected-(U2A-DNU_AB2-PadAB2)") (class "Default")
      (node (ref "U2") (pin "AB2") (pinfunction "DNU_AB2_AB2") (pintype "passive+no_connect"))
    )
    (net (code "100") (name "unconnected-(U2A-DNU_AB11-PadAB11)") (class "Default")
      (node (ref "U2") (pin "AB11") (pinfunction "DNU_AB11_AB11") (pintype "passive+no_connect"))
    )
    (net (code "101") (name "unconnected-(U2A-DNU_AB12-PadAB12)") (class "Default")
      (node (ref "U2") (pin "AB12") (pinfunction "DNU_AB12_AB12") (pintype "passive+no_connect"))
    )
    (net (code "102") (name "unconnected-(U2A-DNU_B1-PadB1)") (class "Default")
      (node (ref "U2") (pin "B1") (pinfunction "DNU_B1_B1") (pintype "passive+no_connect"))
    )
    (net (code "103") (name "unconnected-(U2A-DNU_B12-PadB12)") (class "Default")
      (node (ref "U2") (pin "B12") (pinfunction "DNU_B12_B12") (pintype "passive+no_connect"))
    )
    (net (code "104") (name "unconnected-(U2A-NC_G11-PadG11)") (class "Default")
      (node (ref "U2") (pin "G11") (pinfunction "NC_G11_G11") (pintype "passive+no_connect"))
    )
    (net (code "105") (name "unconnected-(U2A-NC_K5-PadK5)") (class "Default")
      (node (ref "U2") (pin "K5") (pinfunction "NC_K5_K5") (pintype "passive+no_connect"))
    )
    (net (code "106") (name "unconnected-(U2A-NC_K8-PadK8)") (class "Default")
      (node (ref "U2") (pin "K8") (pinfunction "NC_K8_K8") (pintype "passive+no_connect"))
    )
    (net (code "107") (name "unconnected-(U2A-NC_N5-PadN5)") (class "Default")
      (node (ref "U2") (pin "N5") (pinfunction "NC_N5_N5") (pintype "passive+no_connect"))
    )
    (net (code "108") (name "unconnected-(U2A-NC_N8-PadN8)") (class "Default")
      (node (ref "U2") (pin "N8") (pinfunction "NC_N8_N8") (pintype "passive+no_connect"))
    )
  )
)
